# USB_Programmer.net
KiCad netlist of a schematic drawn in Altium Designer
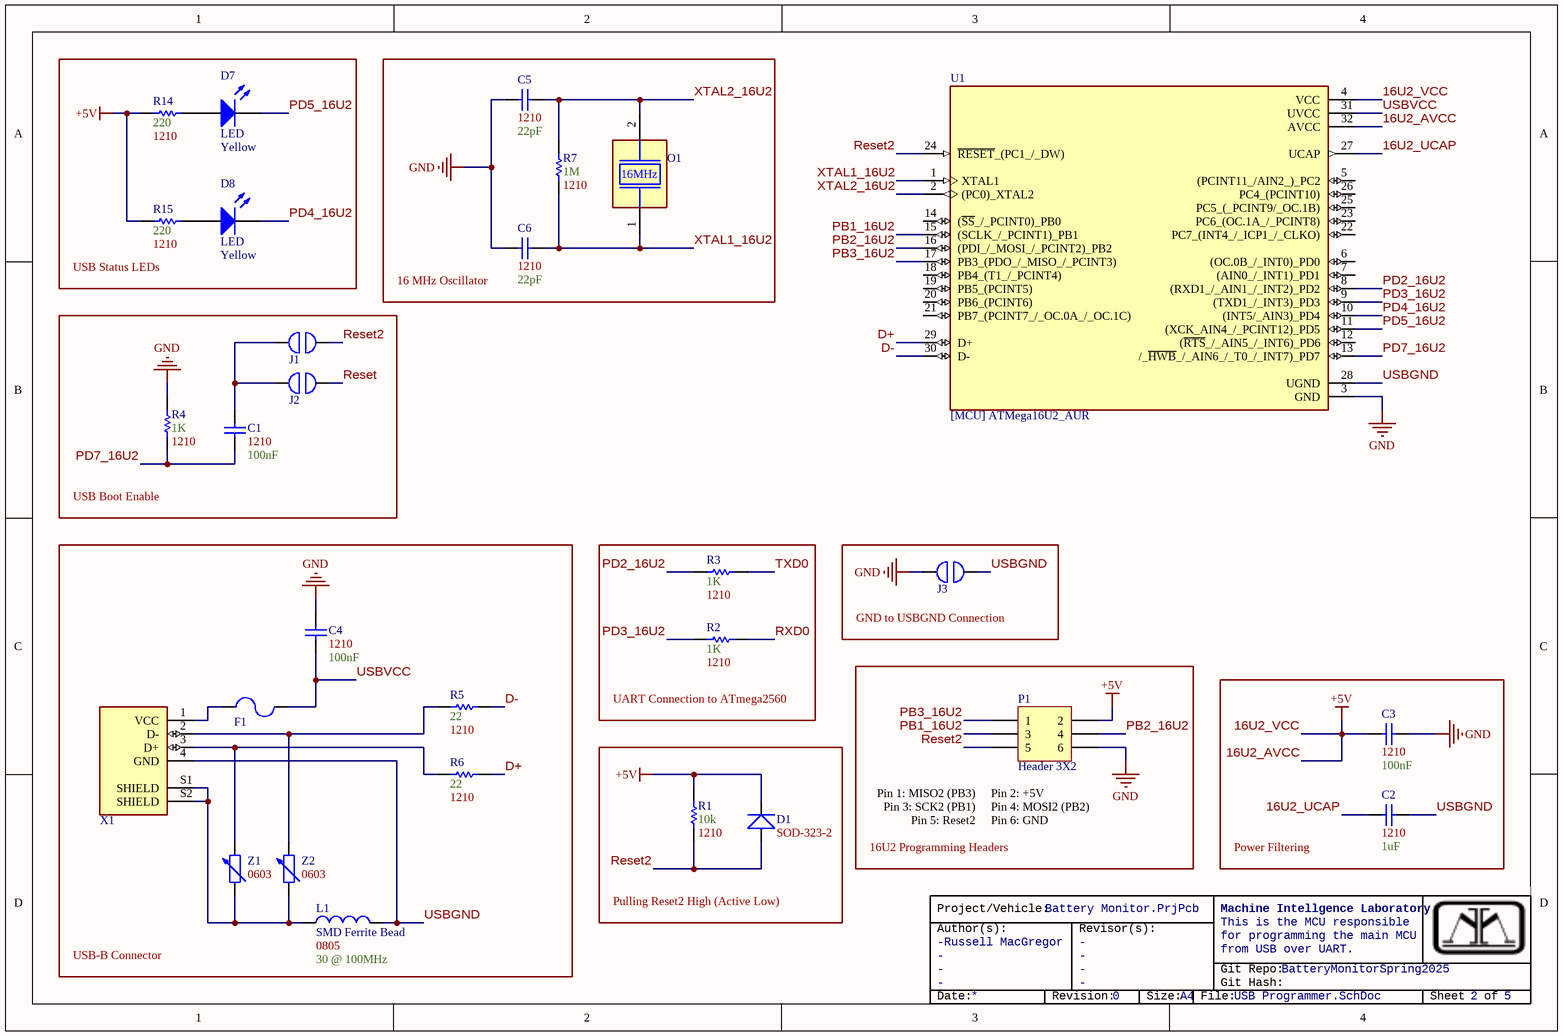
[diagram p0: USB Programmer.SchDoc]

(export (version "E")
  (design (tool "Eeschema 10.0.6"))
  (components
    (comp (ref "C1")
      (value "SMD Cap - Nonpolarized")
      (footprint "SMD Capacitor [1210]")
      (fields
        (field (name "MOUSER PART #") "581-12107C104KAT2A")
        (field (name "SIZE PACKAGE") "1210")
        (field (name "CAPACITANCE") "100nF")
      )
      (libsource (lib "RADM Components") (part "SMD Cap - Nonpolarized"))
    )
    (comp (ref "C2")
      (value "SMD Cap - Nonpolarized")
      (footprint "SMD Capacitor [1210]")
      (fields
        (field (name "MOUSER PART #") "80-C1210X105K5RAUTO")
        (field (name "SIZE PACKAGE") "1210")
        (field (name "CAPACITANCE") "1uF")
      )
      (libsource (lib "RADM Components") (part "SMD Cap - Nonpolarized"))
    )
    (comp (ref "C3")
      (value "SMD Cap - Nonpolarized")
      (footprint "SMD Capacitor [1210]")
      (fields
        (field (name "MOUSER PART #") "581-12107C104KAT2A")
        (field (name "SIZE PACKAGE") "1210")
        (field (name "CAPACITANCE") "100nF")
      )
      (libsource (lib "RADM Components") (part "SMD Cap - Nonpolarized"))
    )
    (comp (ref "C4")
      (value "SMD Cap - Nonpolarized")
      (footprint "SMD Capacitor [1210]")
      (fields
        (field (name "MOUSER PART #") "581-12107C104KAT2A")
        (field (name "SIZE PACKAGE") "1210")
        (field (name "CAPACITANCE") "100nF")
      )
      (libsource (lib "RADM Components") (part "SMD Cap - Nonpolarized"))
    )
    (comp (ref "C5")
      (value "SMD Cap - Nonpolarized")
      (footprint "SMD Capacitor [1210]")
      (fields
        (field (name "MOUSER PART #") "77-VJ1210A220JXGAT5Z")
        (field (name "SIZE PACKAGE") "1210")
        (field (name "CAPACITANCE") "22pF")
      )
      (libsource (lib "RADM Components") (part "SMD Cap - Nonpolarized"))
    )
    (comp (ref "C6")
      (value "SMD Cap - Nonpolarized")
      (footprint "SMD Capacitor [1210]")
      (fields
        (field (name "MOUSER PART #") "77-VJ1210A220JXGAT5Z")
        (field (name "SIZE PACKAGE") "1210")
        (field (name "CAPACITANCE") "22pF")
      )
      (libsource (lib "RADM Components") (part "SMD Cap - Nonpolarized"))
    )
    (comp (ref "D1")
      (value "SMD Diode")
      (footprint "SMD Diode [SOD-323-2]")
      (description "Part #: CD1206-S01575\r\nJLC Part #: C75465")
      (fields (field (name "JLC PART #") "C75465") (field (name "SIZE PACKAGE") "SOD-323-2"))
      (libsource (lib "RADM Components") (part "SMD Diode"))
    )
    (comp (ref "D7")
      (value "LED")
      (footprint "Small Yellow LED")
      (description "3mm LED")
      (fields (field (name "COLOR") "Yellow"))
      (libsource (lib "RADM Components") (part "Small LED"))
    )
    (comp (ref "D8")
      (value "LED")
      (footprint "Small Yellow LED")
      (description "3mm LED")
      (fields (field (name "COLOR") "Yellow"))
      (libsource (lib "RADM Components") (part "Small LED"))
    )
    (comp (ref "F1")
      (value "SMD 500mA Resetable Fuse")
      (footprint "SMD 500mA Resetable Fuse")
      (description "Part #: MF-MSMF050-2\r\nJLC Part #: C17313")
      (fields (field (name "JLC PART #") "C17313"))
      (libsource (lib "RADM Components") (part "SMD 500mA Resetable Fuse"))
    )
    (comp (ref "J1")
      (value "Solderable Jumper")
      (footprint "Solderable Jumper")
      (description "Solderable jumper")
      (libsource (lib "RADM Components") (part "Solderable Jumper"))
    )
    (comp (ref "J2")
      (value "Solderable Jumper")
      (footprint "Solderable Jumper")
      (description "Solderable jumper")
      (libsource (lib "RADM Components") (part "Solderable Jumper"))
    )
    (comp (ref "J3")
      (value "Solderable Jumper")
      (footprint "Solderable Jumper")
      (description "Solderable jumper")
      (libsource (lib "RADM Components") (part "Solderable Jumper"))
    )
    (comp (ref "L1")
      (value "SMD Ferrite Bead")
      (footprint "SMD Ferrite Bead [0805]")
      (description "JLC Part #: C840593 (default)")
      (fields
        (field (name "JLC PART #") "C840593")
        (field (name "SIZE PACKAGE") "0805")
        (field (name "RES @ FREQ") "30 @ 100MHz")
      )
      (libsource (lib "RADM Components") (part "SMD Ferrite Bead"))
    )
    (comp (ref "O1")
      (value "Thru-Hole 16MHz Oscillator")
      (footprint "Thru-Hole 16MHz Oscillator")
      (description "Part #: 2780-HC49US-FF3F18-16.000MHZ-ND (16MHz)\r\nJLC Part #: C6873445")
      (fields (field (name "JLC PART #") "C6873445"))
      (libsource (lib "RADM Components") (part "Thru-Hole 16MHz Oscillator"))
    )
    (comp (ref "P1")
      (value "Header 3X2")
      (footprint "HDR2X3")
      (description "Header, 3-Pin, Dual row")
      (fields (field (name "PUBLISHER") "Altium Limited"))
      (libsource (lib "Miscellaneous Connectors") (part "Header 3X2"))
    )
    (comp (ref "R1")
      (value "SMD Resistor")
      (footprint "SMD Resistor [1210]")
      (description "JLC Part #: C728401\r\n(for 1M Ohm Res)")
      (fields
        (field (name "MOUSER PART #") "71-CRCW121010K0JNAIF")
        (field (name "RESISTANCE") "10k")
        (field (name "SIZE PACKAGE") "1210")
      )
      (libsource (lib "RADM Components") (part "SMD Resistor"))
    )
    (comp (ref "R2")
      (value "SMD Resistor")
      (footprint "SMD Resistor [1210]")
      (fields
        (field (name "MOUSER PART #") "71-CRCW12101K00JNAIF")
        (field (name "RESISTANCE") "1K")
        (field (name "SIZE PACKAGE") "1210")
      )
      (libsource (lib "RADM Components") (part "SMD Resistor"))
    )
    (comp (ref "R3")
      (value "SMD Resistor")
      (footprint "SMD Resistor [1210]")
      (fields
        (field (name "MOUSER PART #") "71-CRCW12101K00JNAIF")
        (field (name "RESISTANCE") "1K")
        (field (name "SIZE PACKAGE") "1210")
      )
      (libsource (lib "RADM Components") (part "SMD Resistor"))
    )
    (comp (ref "R4")
      (value "SMD Resistor")
      (footprint "SMD Resistor [1210]")
      (fields
        (field (name "MOUSER PART #") "71-CRCW12101K00JNAIF")
        (field (name "RESISTANCE") "1K")
        (field (name "SIZE PACKAGE") "1210")
      )
      (libsource (lib "RADM Components") (part "SMD Resistor"))
    )
    (comp (ref "R5")
      (value "SMD Resistor")
      (footprint "SMD Resistor [1210]")
      (fields
        (field (name "MOUSER PART #") "71-CRCW121022R0JNEAH")
        (field (name "RESISTANCE") "22")
        (field (name "SIZE PACKAGE") "1210")
      )
      (libsource (lib "RADM Components") (part "SMD Resistor"))
    )
    (comp (ref "R6")
      (value "SMD Resistor")
      (footprint "SMD Resistor [1210]")
      (fields
        (field (name "MOUSER PART #") "71-CRCW121022R0JNEAH")
        (field (name "RESISTANCE") "22")
        (field (name "SIZE PACKAGE") "1210")
      )
      (libsource (lib "RADM Components") (part "SMD Resistor"))
    )
    (comp (ref "R7")
      (value "SMD Resistor")
      (footprint "SMD Resistor [1210]")
      (description "JLC Part #: C728401\r\n(for 1M Ohm Res)")
      (fields
        (field (name "JLC PART #") "C728401")
        (field (name "MOUSER PART #") "71-CRCW12101M00FKEAH")
        (field (name "RESISTANCE") "1M")
        (field (name "SIZE PACKAGE") "1210")
      )
      (libsource (lib "RADM Components") (part "SMD Resistor"))
    )
    (comp (ref "R14")
      (value "SMD Resistor")
      (footprint "SMD Resistor [1210]")
      (description "JLC Part #: C728401\r\n(for 1M Ohm Res)")
      (fields
        (field (name "MOUSER PART #") "71-CRCW1210220RJNEAH")
        (field (name "RESISTANCE") "220")
        (field (name "SIZE PACKAGE") "1210")
      )
      (libsource (lib "RADM Components") (part "SMD Resistor"))
    )
    (comp (ref "R15")
      (value "SMD Resistor")
      (footprint "SMD Resistor [1210]")
      (description "JLC Part #: C728401\r\n(for 1M Ohm Res)")
      (fields
        (field (name "MOUSER PART #") "71-CRCW1210220RJNEAH")
        (field (name "RESISTANCE") "220")
        (field (name "SIZE PACKAGE") "1210")
      )
      (libsource (lib "RADM Components") (part "SMD Resistor"))
    )
    (comp (ref "U1")
      (value "[MCU] ATMega16U2_AUR")
      (footprint "SMD ATMega16U2_AUR")
      (description "JLC Part #: C507117")
      (fields (field (name "JLC PART #") "C507117"))
      (libsource (lib "RADM Components") (part "[MCU] ATMega16U2_AUR"))
    )
    (comp (ref "X1")
      (value "USB Type-B Female (Thru-Hole)")
      (footprint "USB Type-B Female (Thru-Hole)")
      (description "Part #: USB-B-S-F-B-TH\r\nJLC Part #: C5714571\r\nOUT OF STOCK JLC")
      (fields (field (name "JLC PART #") "C5714571"))
      (libsource (lib "RADM Components") (part "USB Type-B Female (Thru-Hole)"))
    )
    (comp (ref "Z1")
      (value "SMD Varistor")
      (footprint "SMD Varistor [0603]")
      (description "JLC Part #: C840634 (for 0603 size)")
      (fields (field (name "JLC PART #") "C840634") (field (name "SIZE PACKAGE") "0603"))
      (libsource (lib "RADM Components") (part "SMD Varistor"))
    )
    (comp (ref "Z2")
      (value "SMD Varistor")
      (footprint "SMD Varistor [0603]")
      (description "JLC Part #: C840634 (for 0603 size)")
      (fields (field (name "JLC PART #") "C840634") (field (name "SIZE PACKAGE") "0603"))
      (libsource (lib "RADM Components") (part "SMD Varistor"))
    )
  )
  (nets
    (net (code "1") (name "+5V") (class "Default")
      (node (ref "C3") (pin "2") (pinfunction "2_2") (pintype "passive"))
      (node (ref "D1") (pin "C") (pinfunction "C_C") (pintype "power_in"))
      (node (ref "P1") (pin "2") (pinfunction "2_2") (pintype "passive"))
      (node (ref "R1") (pin "2") (pinfunction "2_2") (pintype "passive"))
      (node (ref "R14") (pin "2") (pinfunction "2_2") (pintype "passive"))
      (node (ref "R15") (pin "2") (pinfunction "2_2") (pintype "passive"))
      (node (ref "U1") (pin "32") (pinfunction "AVCC_32") (pintype "power_in"))
      (node (ref "U1") (pin "4") (pinfunction "VCC_4") (pintype "power_in"))
    )
    (net (code "2") (name "/16U2_UCAP") (class "Default")
      (node (ref "C2") (pin "2") (pinfunction "2_2") (pintype "passive"))
      (node (ref "U1") (pin "27") (pinfunction "UCAP_27") (pintype "output"))
    )
    (net (code "3") (name "/D+") (class "Default")
      (node (ref "R6") (pin "2") (pinfunction "2_2") (pintype "passive"))
      (node (ref "U1") (pin "29") (pinfunction "D+_29") (pintype "bidirectional"))
    )
    (net (code "4") (name "/D-") (class "Default")
      (node (ref "R5") (pin "2") (pinfunction "2_2") (pintype "passive"))
      (node (ref "U1") (pin "30") (pinfunction "D-_30") (pintype "bidirectional"))
    )
    (net (code "5") (name "/PB1_16U2") (class "Default")
      (node (ref "P1") (pin "3") (pinfunction "3_3") (pintype "passive"))
      (node (ref "U1") (pin "15") (pinfunction "(SCLK_/_PCINT1)_PB1_15") (pintype "bidirectional"))
    )
    (net (code "6") (name "/PB2_16U2") (class "Default")
      (node (ref "P1") (pin "4") (pinfunction "4_4") (pintype "passive"))
      (node (ref "U1") (pin "16") (pinfunction "(PDI_/_MOSI_/_PCINT2)_PB2_16") (pintype "bidirectional"))
    )
    (net (code "7") (name "/PB3_16U2") (class "Default")
      (node (ref "P1") (pin "1") (pinfunction "1_1") (pintype "passive"))
      (node (ref "U1") (pin "17") (pinfunction "PB3_(PDO_/_MISO_/_PCINT3)_17") (pintype "bidirectional"))
    )
    (net (code "8") (name "/PD2_16U2") (class "Default")
      (node (ref "R3") (pin "2") (pinfunction "2_2") (pintype "passive"))
      (node (ref "U1") (pin "8") (pinfunction "(RXD1_/_AIN1_/_INT2)_PD2_8") (pintype "bidirectional"))
    )
    (net (code "9") (name "/PD3_16U2") (class "Default")
      (node (ref "R2") (pin "2") (pinfunction "2_2") (pintype "passive"))
      (node (ref "U1") (pin "9") (pinfunction "(TXD1_/_INT3)_PD3_9") (pintype "bidirectional"))
    )
    (net (code "10") (name "/PD4_16U2") (class "Default")
      (node (ref "D8") (pin "2") (pinfunction "K_2") (pintype "passive"))
      (node (ref "U1") (pin "10") (pinfunction "(INT5/_AIN3)_PD4_10") (pintype "bidirectional"))
    )
    (net (code "11") (name "/PD5_16U2") (class "Default")
      (node (ref "D7") (pin "2") (pinfunction "K_2") (pintype "passive"))
      (node (ref "U1") (pin "11") (pinfunction "(XCK_AIN4_/_PCINT12)_PD5_11") (pintype "bidirectional"))
    )
    (net (code "12") (name "/PD7_16U2") (class "Default")
      (node (ref "C1") (pin "1") (pinfunction "1_1") (pintype "passive"))
      (node (ref "R4") (pin "1") (pinfunction "1_1") (pintype "passive"))
      (node (ref "U1") (pin "13") (pinfunction "/_~{HWB}_/_AIN6_/_T0_/_INT7)_PD7_13") (pintype "bidirectional"))
    )
    (net (code "13") (name "/RXD0") (class "Default")
      (node (ref "R2") (pin "1") (pinfunction "1_1") (pintype "passive"))
    )
    (net (code "14") (name "/Reset") (class "Default") (node (ref "J2") (pin "2") (pintype "passive")))
    (net (code "15") (name "/Reset2") (class "Default")
      (node (ref "D1") (pin "A") (pinfunction "A_A") (pintype "power_in"))
      (node (ref "J1") (pin "2") (pintype "passive"))
      (node (ref "P1") (pin "5") (pinfunction "5_5") (pintype "passive"))
      (node (ref "R1") (pin "1") (pinfunction "1_1") (pintype "passive"))
      (node (ref "U1") (pin "24") (pinfunction "~{RESET}_(PC1_/_DW)_24") (pintype "input"))
    )
    (net (code "16") (name "/TXD0") (class "Default")
      (node (ref "R3") (pin "1") (pinfunction "1_1") (pintype "passive"))
    )
    (net (code "17") (name "/USBGND") (class "Default")
      (node (ref "C2") (pin "1") (pinfunction "1_1") (pintype "passive"))
      (node (ref "J3") (pin "2") (pintype "passive"))
      (node (ref "L1") (pin "2") (pinfunction "2_2") (pintype "passive"))
      (node (ref "U1") (pin "28") (pinfunction "UGND_28") (pintype "power_in"))
      (node (ref "X1") (pin "4") (pinfunction "GND_4") (pintype "power_in"))
    )
    (net (code "18") (name "/USBVCC") (class "Default")
      (node (ref "C4") (pin "1") (pinfunction "1_1") (pintype "passive"))
      (node (ref "F1") (pin "2") (pinfunction "2_2") (pintype "passive"))
      (node (ref "U1") (pin "31") (pinfunction "UVCC_31") (pintype "power_in"))
    )
    (net (code "19") (name "/XTAL1_16U2") (class "Default")
      (node (ref "C6") (pin "1") (pinfunction "1_1") (pintype "passive"))
      (node (ref "O1") (pin "1") (pinfunction "1_1") (pintype "passive"))
      (node (ref "R7") (pin "1") (pinfunction "1_1") (pintype "passive"))
      (node (ref "U1") (pin "1") (pinfunction "XTAL1_1") (pintype "input"))
    )
    (net (code "20") (name "/XTAL2_16U2") (class "Default")
      (node (ref "C5") (pin "1") (pinfunction "1_1") (pintype "passive"))
      (node (ref "O1") (pin "2") (pinfunction "2_2") (pintype "passive"))
      (node (ref "R7") (pin "2") (pinfunction "2_2") (pintype "passive"))
      (node (ref "U1") (pin "2") (pinfunction "(PC0)_XTAL2_2") (pintype "output"))
    )
    (net (code "21") (name "GND") (class "Default")
      (node (ref "C3") (pin "1") (pinfunction "1_1") (pintype "passive"))
      (node (ref "C4") (pin "2") (pinfunction "2_2") (pintype "passive"))
      (node (ref "C5") (pin "2") (pinfunction "2_2") (pintype "passive"))
      (node (ref "C6") (pin "2") (pinfunction "2_2") (pintype "passive"))
      (node (ref "J3") (pin "1") (pintype "passive"))
      (node (ref "P1") (pin "6") (pinfunction "6_6") (pintype "passive"))
      (node (ref "R4") (pin "2") (pinfunction "2_2") (pintype "passive"))
      (node (ref "U1") (pin "3") (pinfunction "GND_3") (pintype "power_in"))
    )
    (net (code "22") (name "Net-(C1-Pad2)") (class "Default")
      (node (ref "C1") (pin "2") (pinfunction "2_2") (pintype "passive"))
      (node (ref "J1") (pin "1") (pintype "passive"))
      (node (ref "J2") (pin "1") (pintype "passive"))
    )
    (net (code "23") (name "Net-(D7-A)") (class "Default")
      (node (ref "D7") (pin "1") (pinfunction "A_1") (pintype "passive"))
      (node (ref "R14") (pin "1") (pinfunction "1_1") (pintype "passive"))
    )
    (net (code "24") (name "Net-(D8-A)") (class "Default")
      (node (ref "D8") (pin "1") (pinfunction "A_1") (pintype "passive"))
      (node (ref "R15") (pin "1") (pinfunction "1_1") (pintype "passive"))
    )
    (net (code "25") (name "Net-(L1-Pad1)") (class "Default")
      (node (ref "L1") (pin "1") (pinfunction "1_1") (pintype "passive"))
      (node (ref "X1") (pin "S1") (pinfunction "SHIELD_S1") (pintype "passive"))
      (node (ref "X1") (pin "S2") (pinfunction "SHIELD_S2") (pintype "passive"))
      (node (ref "Z1") (pin "1") (pinfunction "1_1") (pintype "passive"))
      (node (ref "Z2") (pin "1") (pinfunction "1_1") (pintype "passive"))
    )
    (net (code "26") (name "Net-(X1-D+)") (class "Default")
      (node (ref "R6") (pin "1") (pinfunction "1_1") (pintype "passive"))
      (node (ref "X1") (pin "3") (pinfunction "D+_3") (pintype "bidirectional"))
      (node (ref "Z1") (pin "2") (pinfunction "2_2") (pintype "passive"))
    )
    (net (code "27") (name "Net-(X1-D-)") (class "Default")
      (node (ref "R5") (pin "1") (pinfunction "1_1") (pintype "passive"))
      (node (ref "X1") (pin "2") (pinfunction "D-_2") (pintype "bidirectional"))
      (node (ref "Z2") (pin "2") (pinfunction "2_2") (pintype "passive"))
    )
    (net (code "28") (name "Net-(X1-VCC)") (class "Default")
      (node (ref "F1") (pin "1") (pinfunction "1_1") (pintype "passive"))
      (node (ref "X1") (pin "1") (pinfunction "VCC_1") (pintype "power_in"))
    )
    (net (code "29") (name "unconnected-(U1-(AIN0_{slash}_INT1)_PD1-Pad7)") (class "Default")
      (node (ref "U1") (pin "7") (pinfunction "(AIN0_/_INT1)_PD1_7") (pintype "bidirectional"))
    )
    (net (code "30") (name "unconnected-(U1-(OC.0B_{slash}_INT0)_PD0-Pad6)") (class "Default")
      (node (ref "U1") (pin "6") (pinfunction "(OC.0B_/_INT0)_PD0_6") (pintype "bidirectional"))
    )
    (net (code "31") (name "unconnected-(U1-(PCINT11_{slash}AIN2_)_PC2-Pad5)") (class "Default")
      (node (ref "U1") (pin "5") (pinfunction "(PCINT11_/AIN2_)_PC2_5") (pintype "bidirectional"))
    )
    (net (code "32") (name "unconnected-(U1-(~{RTS}_{slash}_AIN5_{slash}_INT6)_PD6-Pad12)") (class "Default")
      (node (ref "U1") (pin "12") (pinfunction "(~{RTS}_/_AIN5_/_INT6)_PD6_12") (pintype "bidirectional"))
    )
    (net (code "33") (name "unconnected-(U1-(~{SS}_{slash}_PCINT0)_PB0-Pad14)") (class "Default")
      (node (ref "U1") (pin "14") (pinfunction "(~{SS}_/_PCINT0)_PB0_14") (pintype "bidirectional"))
    )
    (net (code "34") (name "unconnected-(U1-PB4_(T1_{slash}_PCINT4)-Pad18)") (class "Default")
      (node (ref "U1") (pin "18") (pinfunction "PB4_(T1_/_PCINT4)_18") (pintype "bidirectional"))
    )
    (net (code "35") (name "unconnected-(U1-PB5_(PCINT5)-Pad19)") (class "Default")
      (node (ref "U1") (pin "19") (pinfunction "PB5_(PCINT5)_19") (pintype "bidirectional"))
    )
    (net (code "36") (name "unconnected-(U1-PB6_(PCINT6)-Pad20)") (class "Default")
      (node (ref "U1") (pin "20") (pinfunction "PB6_(PCINT6)_20") (pintype "bidirectional"))
    )
    (net (code "37") (name "unconnected-(U1-PB7_(PCINT7_{slash}_OC.0A_{slash}_OC.1C)-Pad21)") (class "Default")
      (node (ref "U1") (pin "21") (pinfunction "PB7_(PCINT7_/_OC.0A_/_OC.1C)_21") (pintype "bidirectional"))
    )
    (net (code "38") (name "unconnected-(U1-PC4_(PCINT10)-Pad26)") (class "Default")
      (node (ref "U1") (pin "26") (pinfunction "PC4_(PCINT10)_26") (pintype "bidirectional"))
    )
    (net (code "39") (name "unconnected-(U1-PC5_(_PCINT9{slash}_OC.1B)-Pad25)") (class "Default")
      (node (ref "U1") (pin "25") (pinfunction "PC5_(_PCINT9/_OC.1B)_25") (pintype "bidirectional"))
    )
    (net (code "40") (name "unconnected-(U1-PC6_(OC.1A_{slash}_PCINT8)-Pad23)") (class "Default")
      (node (ref "U1") (pin "23") (pinfunction "PC6_(OC.1A_/_PCINT8)_23") (pintype "bidirectional"))
    )
    (net (code "41") (name "unconnected-(U1-PC7_(INT4_{slash}_ICP1_{slash}_CLKO)-Pad22)") (class "Default")
      (node (ref "U1") (pin "22") (pinfunction "PC7_(INT4_/_ICP1_/_CLKO)_22") (pintype "bidirectional"))
    )
  )
)
